# ProiectTSC_schematic.net
KiCad netlist of a schematic drawn in EAGLE
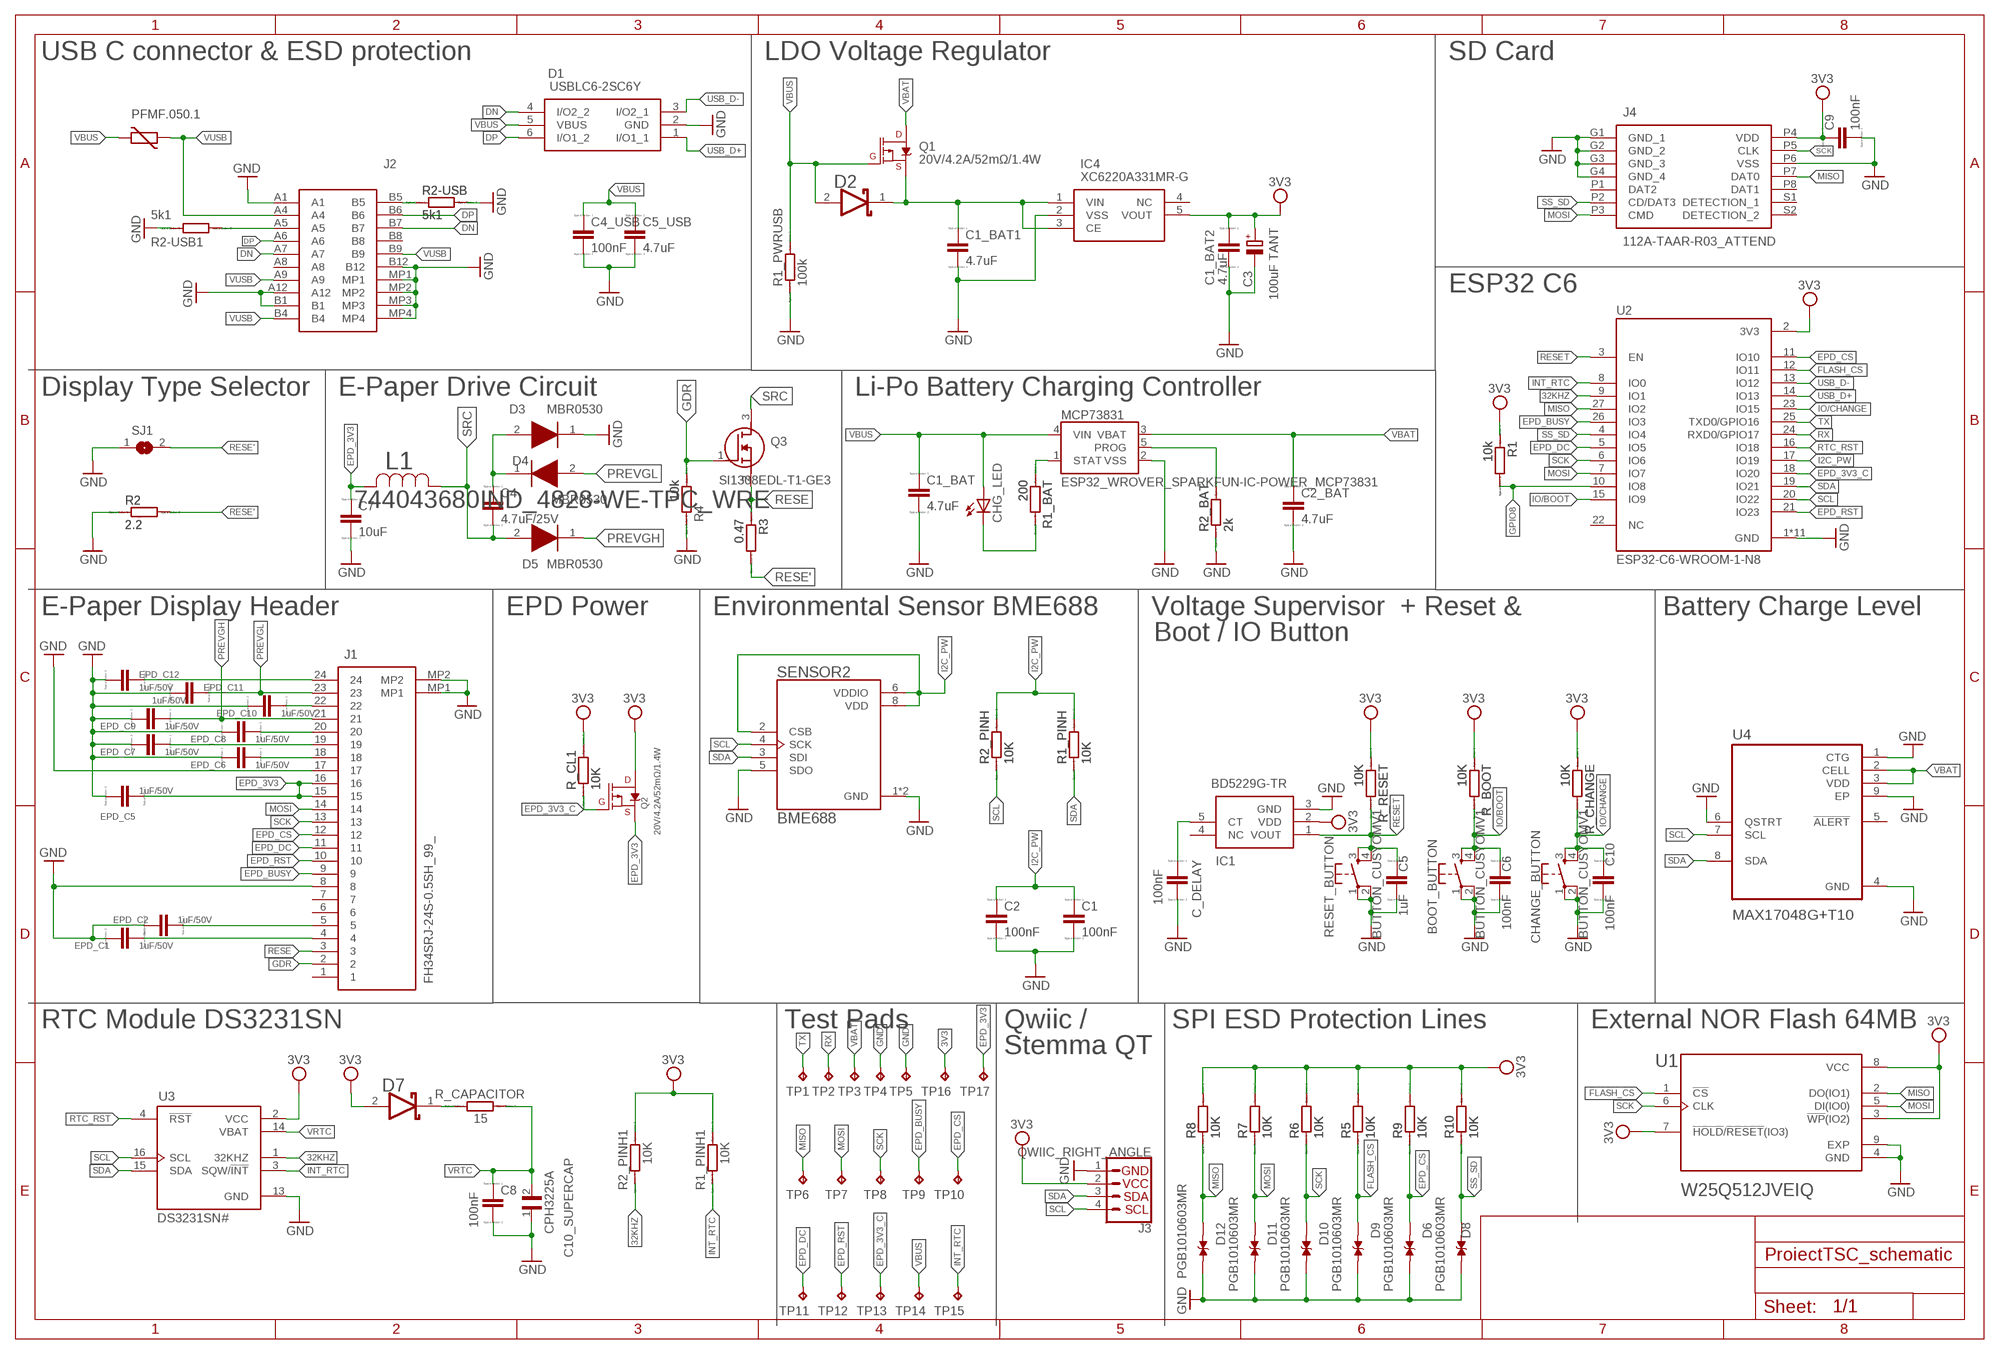
[diagram p0: schematic, sheet 1]

(export (version "E")
  (design (tool "Eeschema 10.0.6"))
  (components
    (comp (ref "BOOT_BUTTON")
      (value "BUTTON_CUSYOMV1")
      (footprint "eagle-import:MYBUTTON")
      (libsource (lib "eagle-import") (part "BUTTON_CUSYOMV1"))
    )
    (comp (ref "C1")
      (value "100nF")
      (footprint "eagle-import:ESP32_WROVER_EAGLE-LTSPICE_C0402")
      (libsource (lib "eagle-import") (part "ESP32_WROVER_EAGLE-LTSPICE_CC0402"))
    )
    (comp (ref "C1_BAT")
      (value "4.7uF")
      (footprint "eagle-import:ESP32_WROVER_EAGLE-LTSPICE_C0402")
      (libsource (lib "eagle-import") (part "ESP32_WROVER_EAGLE-LTSPICE_CC0402"))
    )
    (comp (ref "C1_BAT1")
      (value "4.7uF")
      (footprint "eagle-import:ESP32_WROVER_EAGLE-LTSPICE_C0402")
      (libsource (lib "eagle-import") (part "ESP32_WROVER_EAGLE-LTSPICE_CC0402"))
    )
    (comp (ref "C1_BAT2")
      (value "4.7uF")
      (footprint "eagle-import:ESP32_WROVER_EAGLE-LTSPICE_C0402")
      (libsource (lib "eagle-import") (part "ESP32_WROVER_EAGLE-LTSPICE_CC0402"))
    )
    (comp (ref "C2")
      (value "100nF")
      (footprint "eagle-import:ESP32_WROVER_EAGLE-LTSPICE_C0402")
      (libsource (lib "eagle-import") (part "ESP32_WROVER_EAGLE-LTSPICE_CC0402"))
    )
    (comp (ref "C2_BAT")
      (value "4.7uF")
      (footprint "eagle-import:ESP32_WROVER_EAGLE-LTSPICE_C0402")
      (libsource (lib "eagle-import") (part "ESP32_WROVER_EAGLE-LTSPICE_CC0402"))
    )
    (comp (ref "C3")
      (value "100uF TANT")
      (footprint "eagle-import:RCL_CT3528")
      (libsource (lib "eagle-import") (part "RCL_CPOL-EUCT3528"))
    )
    (comp (ref "C4")
      (value "4.7uF/25V")
      (footprint "eagle-import:ESP32_WROVER_EAGLE-LTSPICE_C0402")
      (libsource (lib "eagle-import") (part "ESP32_WROVER_EAGLE-LTSPICE_CC0402"))
    )
    (comp (ref "C4_USB")
      (value "100nF")
      (footprint "eagle-import:ESP32_WROVER_EAGLE-LTSPICE_C0402")
      (libsource (lib "eagle-import") (part "ESP32_WROVER_EAGLE-LTSPICE_CC0402"))
    )
    (comp (ref "C5")
      (value "1uF")
      (footprint "eagle-import:ESP32_WROVER_EAGLE-LTSPICE_C0402")
      (libsource (lib "eagle-import") (part "ESP32_WROVER_EAGLE-LTSPICE_CC0402"))
    )
    (comp (ref "C5_USB")
      (value "4.7uF")
      (footprint "eagle-import:ESP32_WROVER_EAGLE-LTSPICE_C0402")
      (libsource (lib "eagle-import") (part "ESP32_WROVER_EAGLE-LTSPICE_CC0402"))
    )
    (comp (ref "C6")
      (value "100nF")
      (footprint "eagle-import:ESP32_WROVER_EAGLE-LTSPICE_C0402")
      (libsource (lib "eagle-import") (part "ESP32_WROVER_EAGLE-LTSPICE_CC0402"))
    )
    (comp (ref "C7")
      (value "10uF")
      (footprint "eagle-import:ESP32_WROVER_EAGLE-LTSPICE_C0402")
      (libsource (lib "eagle-import") (part "ESP32_WROVER_EAGLE-LTSPICE_CC0402"))
    )
    (comp (ref "C8")
      (value "100nF")
      (footprint "eagle-import:ESP32_WROVER_EAGLE-LTSPICE_C0402")
      (libsource (lib "eagle-import") (part "ESP32_WROVER_EAGLE-LTSPICE_CC0402"))
    )
    (comp (ref "C9")
      (value "100nF")
      (footprint "eagle-import:ESP32_WROVER_EAGLE-LTSPICE_C0402")
      (libsource (lib "eagle-import") (part "ESP32_WROVER_EAGLE-LTSPICE_CC0402"))
    )
    (comp (ref "C10")
      (value "100nF")
      (footprint "eagle-import:ESP32_WROVER_EAGLE-LTSPICE_C0402")
      (libsource (lib "eagle-import") (part "ESP32_WROVER_EAGLE-LTSPICE_CC0402"))
    )
    (comp (ref "C10_SUPERCAP")
      (value "CPH3225A")
      (footprint "eagle-import:CAPCP3225X100N")
      (fields (field (name "MF") "Seiko Instruments"))
      (libsource (lib "eagle-import") (part "CPH3225A"))
    )
    (comp (ref "CHANGE_BUTTON")
      (value "BUTTON_CUSYOMV1")
      (footprint "eagle-import:MYBUTTON")
      (libsource (lib "eagle-import") (part "BUTTON_CUSYOMV1"))
    )
    (comp (ref "CHG_LED")
      (value "ADAFRUIT_LEDCHIP-LED0603")
      (footprint "eagle-import:ADAFRUIT_CHIP-LED0603")
      (libsource (lib "eagle-import") (part "ADAFRUIT_LEDCHIP-LED0603"))
    )
    (comp (ref "C_DELAY")
      (value "100nF")
      (footprint "eagle-import:ESP32_WROVER_EAGLE-LTSPICE_C0402")
      (libsource (lib "eagle-import") (part "ESP32_WROVER_EAGLE-LTSPICE_CC0402"))
    )
    (comp (ref "D1")
      (value "USBLC6-2SC6Y")
      (footprint "eagle-import:SOT95P280X145-6N")
      (fields (field (name "MF") "STMicroelectronics"))
      (libsource (lib "eagle-import") (part "USBLC6-2SC6Y"))
    )
    (comp (ref "D2")
      (value "SD0805S020S1R0")
      (footprint "eagle-import:ESP32_WROVER_AVX---SD0805S020S1R0_AVX_SD0805S020S1R0_0")
      (fields
        (field (name "DIGIKEY_PART_NUMBER") "478-7800-1-ND")
        (field (name "MF") "AVX")
        (field (name "MOUSER_PART_NUMBER") "581-SD0805S020S1R0")
      )
      (libsource (lib "eagle-import") (part "ESP32_WROVER_AVX---SD0805S020S1R0_AVX_SD0805S020S1R0_0_0AVX_SD0805S020S1R0_0_0"))
    )
    (comp (ref "D3")
      (value "MBR0530")
      (footprint "eagle-import:SOD3716X135N")
      (fields (field (name "MF") "ON Semiconductor"))
      (libsource (lib "eagle-import") (part "MBR0530"))
    )
    (comp (ref "D4")
      (value "MBR0530")
      (footprint "eagle-import:SOD3716X135N")
      (fields (field (name "MF") "ON Semiconductor"))
      (libsource (lib "eagle-import") (part "MBR0530"))
    )
    (comp (ref "D5")
      (value "MBR0530")
      (footprint "eagle-import:SOD3716X135N")
      (fields (field (name "MF") "ON Semiconductor"))
      (libsource (lib "eagle-import") (part "MBR0530"))
    )
    (comp (ref "D6")
      (value "PGB1010603MR")
      (footprint "eagle-import:DIOC1608X36N")
      (fields (field (name "MF") "Littelfuse Inc."))
      (libsource (lib "eagle-import") (part "PGB1010603MR"))
    )
    (comp (ref "D7")
      (value "SD0805S020S1R0")
      (footprint "eagle-import:ESP32_WROVER_AVX---SD0805S020S1R0_AVX_SD0805S020S1R0_0")
      (fields
        (field (name "DIGIKEY_PART_NUMBER") "478-7800-1-ND")
        (field (name "MF") "AVX")
        (field (name "MOUSER_PART_NUMBER") "581-SD0805S020S1R0")
      )
      (libsource (lib "eagle-import") (part "ESP32_WROVER_AVX---SD0805S020S1R0_AVX_SD0805S020S1R0_0_0AVX_SD0805S020S1R0_0_0"))
    )
    (comp (ref "D8")
      (value "PGB1010603MR")
      (footprint "eagle-import:DIOC1608X36N")
      (fields (field (name "MF") "Littelfuse Inc."))
      (libsource (lib "eagle-import") (part "PGB1010603MR"))
    )
    (comp (ref "D9")
      (value "PGB1010603MR")
      (footprint "eagle-import:DIOC1608X36N")
      (fields (field (name "MF") "Littelfuse Inc."))
      (libsource (lib "eagle-import") (part "PGB1010603MR"))
    )
    (comp (ref "D10")
      (value "PGB1010603MR")
      (footprint "eagle-import:DIOC1608X36N")
      (fields (field (name "MF") "Littelfuse Inc."))
      (libsource (lib "eagle-import") (part "PGB1010603MR"))
    )
    (comp (ref "D11")
      (value "PGB1010603MR")
      (footprint "eagle-import:DIOC1608X36N")
      (fields (field (name "MF") "Littelfuse Inc."))
      (libsource (lib "eagle-import") (part "PGB1010603MR"))
    )
    (comp (ref "D12")
      (value "PGB1010603MR")
      (footprint "eagle-import:DIOC1608X36N")
      (fields (field (name "MF") "Littelfuse Inc."))
      (libsource (lib "eagle-import") (part "PGB1010603MR"))
    )
    (comp (ref "EPD_C1")
      (value "1uF/50V")
      (footprint "eagle-import:ESP32_WROVER_EAGLE-LTSPICE_C0402")
      (libsource (lib "eagle-import") (part "ESP32_WROVER_EAGLE-LTSPICE_CC0402"))
    )
    (comp (ref "EPD_C2")
      (value "1uF/50V")
      (footprint "eagle-import:ESP32_WROVER_EAGLE-LTSPICE_C0402")
      (libsource (lib "eagle-import") (part "ESP32_WROVER_EAGLE-LTSPICE_CC0402"))
    )
    (comp (ref "EPD_C5")
      (value "1uF/50V")
      (footprint "eagle-import:ESP32_WROVER_EAGLE-LTSPICE_C0402")
      (libsource (lib "eagle-import") (part "ESP32_WROVER_EAGLE-LTSPICE_CC0402"))
    )
    (comp (ref "EPD_C6")
      (value "1uF/50V")
      (footprint "eagle-import:ESP32_WROVER_EAGLE-LTSPICE_C0402")
      (libsource (lib "eagle-import") (part "ESP32_WROVER_EAGLE-LTSPICE_CC0402"))
    )
    (comp (ref "EPD_C7")
      (value "1uF/50V")
      (footprint "eagle-import:ESP32_WROVER_EAGLE-LTSPICE_C0402")
      (libsource (lib "eagle-import") (part "ESP32_WROVER_EAGLE-LTSPICE_CC0402"))
    )
    (comp (ref "EPD_C8")
      (value "1uF/50V")
      (footprint "eagle-import:ESP32_WROVER_EAGLE-LTSPICE_C0402")
      (libsource (lib "eagle-import") (part "ESP32_WROVER_EAGLE-LTSPICE_CC0402"))
    )
    (comp (ref "EPD_C9")
      (value "1uF/50V")
      (footprint "eagle-import:ESP32_WROVER_EAGLE-LTSPICE_C0402")
      (libsource (lib "eagle-import") (part "ESP32_WROVER_EAGLE-LTSPICE_CC0402"))
    )
    (comp (ref "EPD_C10")
      (value "1uF/50V")
      (footprint "eagle-import:ESP32_WROVER_EAGLE-LTSPICE_C0402")
      (libsource (lib "eagle-import") (part "ESP32_WROVER_EAGLE-LTSPICE_CC0402"))
    )
    (comp (ref "EPD_C11")
      (value "1uF/50V")
      (footprint "eagle-import:ESP32_WROVER_EAGLE-LTSPICE_C0402")
      (libsource (lib "eagle-import") (part "ESP32_WROVER_EAGLE-LTSPICE_CC0402"))
    )
    (comp (ref "EPD_C12")
      (value "1uF/50V")
      (footprint "eagle-import:ESP32_WROVER_EAGLE-LTSPICE_C0402")
      (libsource (lib "eagle-import") (part "ESP32_WROVER_EAGLE-LTSPICE_CC0402"))
    )
    (comp (ref "IC1")
      (value "BD5229G-TR")
      (footprint "eagle-import:SOT95P280X120-5N")
      (fields (field (name "MOUSER_PART_NUMBER") "755-BD5229G-TR"))
      (libsource (lib "eagle-import") (part "BD5229G-TR"))
    )
    (comp (ref "IC4")
      (value "XC6220A331MR-G")
      (footprint "eagle-import:SOT95P280X120-5N")
      (fields (field (name "MOUSER_PART_NUMBER") "865-XC6220A331MR-G"))
      (libsource (lib "eagle-import") (part "XC6220A331MR-G"))
    )
    (comp (ref "J1")
      (value "FH34SRJ-24S-0.5SH_99_")
      (footprint "eagle-import:FH34SRJ24S05SH99")
      (fields
        (field (name "MANUFACTURER_PART_NUMBER") "FH34SRJ-24S-0.5SH(99)")
        (field (name "MOUSER_PART_NUMBER") "798-FH34SRJ24S05SH99")
      )
      (libsource (lib "eagle-import") (part "FH34SRJ-24S-0.5SH_99_"))
    )
    (comp (ref "J2")
      (value "SAMACSYS_PARTS_USB4110-GF-A")
      (footprint "eagle-import:SAMACSYS_PARTS_USB4110GFA")
      (fields
        (field (name "MANUFACTURER_PART_NUMBER") "USB4110-GF-A")
        (field (name "MOUSER_PART_NUMBER") "640-USB4110-GF-A")
      )
      (libsource (lib "eagle-import") (part "SAMACSYS_PARTS_USB4110-GF-A"))
    )
    (comp (ref "J3")
      (value "QWIIC_RIGHT_ANGLE")
      (footprint "eagle-import:JST04_1MM_RA")
      (libsource (lib "eagle-import") (part "QWIIC_CONNECTORJS-1MM"))
    )
    (comp (ref "J4")
      (value "112A-TAAR-R03_ATTEND")
      (footprint "eagle-import:112ATAARR03ATTEND")
      (fields (field (name "MANUFACTURER_PART_NUMBER") "112A-TAAR-R03 ATTEND"))
      (libsource (lib "eagle-import") (part "112A-TAAR-R03_ATTEND"))
    )
    (comp (ref "L1")
      (value "744043680IND_4828-WE-TPC_WRE")
      (footprint "eagle-import:IND_4828-WE-TPC_WRE")
      (fields
        (field (name "MANUFACTURER_PART_NUMBER") "744043680")
        (field (name "COPYRIGHT") "Copyright (C) 2024 Ultra Librarian. All rights reserved.")
      )
      (libsource (lib "eagle-import") (part "744043680IND_4828-WE-TPC_WRE"))
    )
    (comp (ref "MCP73831")
      (value "ESP32_WROVER_SPARKFUN-IC-POWER_MCP73831")
      (footprint "eagle-import:ESP32_WROVER_SPARKFUN-IC-POWER_SOT23-5")
      (libsource (lib "eagle-import") (part "ESP32_WROVER_SPARKFUN-IC-POWER_MCP73831"))
    )
    (comp (ref "PFMF.050.1")
      (value "ESP32C6_VARISTORCN1812")
      (footprint "eagle-import:ESP32C6_VARISTOR_CT_CN1812")
      (libsource (lib "eagle-import") (part "ESP32C6_VARISTORCN1812"))
    )
    (comp (ref "Q1")
      (value "20V/4.2A/52mΩ/1.4W")
      (footprint "eagle-import:ESP32_WROVER_SPARKFUN-DISCRETESEMI_SOT23-3")
      (libsource (lib "eagle-import") (part "ESP32_WROVER_SPARKFUN-DISCRETESEMI_MOSFET_PCH-DMG2305UX-7"))
    )
    (comp (ref "Q2")
      (value "20V/4.2A/52mΩ/1.4W")
      (footprint "eagle-import:ESP32_WROVER_SPARKFUN-DISCRETESEMI_SOT23-3")
      (libsource (lib "eagle-import") (part "ESP32_WROVER_SPARKFUN-DISCRETESEMI_MOSFET_PCH-DMG2305UX-7"))
    )
    (comp (ref "Q3")
      (value "SI1308EDL-T1-GE3")
      (footprint "eagle-import:SOT65P210X110-3N")
      (fields (field (name "MF") "Vishay Siliconix"))
      (libsource (lib "eagle-import") (part "SI1308EDL-T1-GE3"))
    )
    (comp (ref "R1")
      (value "10k")
      (footprint "eagle-import:ESP32_WROVER_EAGLE-LTSPICE_R0402")
      (libsource (lib "eagle-import") (part "ESP32_WROVER_EAGLE-LTSPICE_RR0402"))
    )
    (comp (ref "R1_BAT")
      (value "200")
      (footprint "eagle-import:ESP32_WROVER_EAGLE-LTSPICE_R0402")
      (libsource (lib "eagle-import") (part "ESP32_WROVER_EAGLE-LTSPICE_RR0402"))
    )
    (comp (ref "R1_PINH")
      (value "10K")
      (footprint "eagle-import:ESP32_WROVER_EAGLE-LTSPICE_R0402")
      (libsource (lib "eagle-import") (part "ESP32_WROVER_EAGLE-LTSPICE_RR0402"))
    )
    (comp (ref "R1_PINH1")
      (value "10K")
      (footprint "eagle-import:ESP32_WROVER_EAGLE-LTSPICE_R0402")
      (libsource (lib "eagle-import") (part "ESP32_WROVER_EAGLE-LTSPICE_RR0402"))
    )
    (comp (ref "R1_PWRUSB")
      (value "100k")
      (footprint "eagle-import:ESP32_WROVER_EAGLE-LTSPICE_R0402")
      (libsource (lib "eagle-import") (part "ESP32_WROVER_EAGLE-LTSPICE_RR0402"))
    )
    (comp (ref "R2")
      (value "2.2")
      (footprint "eagle-import:ESP32_WROVER_EAGLE-LTSPICE_R0402")
      (libsource (lib "eagle-import") (part "ESP32_WROVER_EAGLE-LTSPICE_RR0402"))
    )
    (comp (ref "R2-USB")
      (value "5k1")
      (footprint "eagle-import:ESP32_WROVER_EAGLE-LTSPICE_R0402")
      (libsource (lib "eagle-import") (part "ESP32_WROVER_EAGLE-LTSPICE_RR0402"))
    )
    (comp (ref "R2-USB1")
      (value "5k1")
      (footprint "eagle-import:ESP32_WROVER_EAGLE-LTSPICE_R0402")
      (libsource (lib "eagle-import") (part "ESP32_WROVER_EAGLE-LTSPICE_RR0402"))
    )
    (comp (ref "R2_BAT")
      (value "2k")
      (footprint "eagle-import:ESP32_WROVER_EAGLE-LTSPICE_R0402")
      (libsource (lib "eagle-import") (part "ESP32_WROVER_EAGLE-LTSPICE_RR0402"))
    )
    (comp (ref "R2_PINH")
      (value "10K")
      (footprint "eagle-import:ESP32_WROVER_EAGLE-LTSPICE_R0402")
      (libsource (lib "eagle-import") (part "ESP32_WROVER_EAGLE-LTSPICE_RR0402"))
    )
    (comp (ref "R2_PINH1")
      (value "10K")
      (footprint "eagle-import:ESP32_WROVER_EAGLE-LTSPICE_R0402")
      (libsource (lib "eagle-import") (part "ESP32_WROVER_EAGLE-LTSPICE_RR0402"))
    )
    (comp (ref "R3")
      (value "0.47")
      (footprint "eagle-import:ESP32_WROVER_EAGLE-LTSPICE_R0402")
      (libsource (lib "eagle-import") (part "ESP32_WROVER_EAGLE-LTSPICE_RR0402"))
    )
    (comp (ref "R4")
      (value "10k")
      (footprint "eagle-import:ESP32_WROVER_EAGLE-LTSPICE_R0402")
      (libsource (lib "eagle-import") (part "ESP32_WROVER_EAGLE-LTSPICE_RR0402"))
    )
    (comp (ref "R5")
      (value "10K")
      (footprint "eagle-import:ESP32_WROVER_EAGLE-LTSPICE_R0402")
      (libsource (lib "eagle-import") (part "ESP32_WROVER_EAGLE-LTSPICE_RR0402"))
    )
    (comp (ref "R6")
      (value "10K")
      (footprint "eagle-import:ESP32_WROVER_EAGLE-LTSPICE_R0402")
      (libsource (lib "eagle-import") (part "ESP32_WROVER_EAGLE-LTSPICE_RR0402"))
    )
    (comp (ref "R7")
      (value "10K")
      (footprint "eagle-import:ESP32_WROVER_EAGLE-LTSPICE_R0402")
      (libsource (lib "eagle-import") (part "ESP32_WROVER_EAGLE-LTSPICE_RR0402"))
    )
    (comp (ref "R8")
      (value "10K")
      (footprint "eagle-import:ESP32_WROVER_EAGLE-LTSPICE_R0402")
      (libsource (lib "eagle-import") (part "ESP32_WROVER_EAGLE-LTSPICE_RR0402"))
    )
    (comp (ref "R9")
      (value "10K")
      (footprint "eagle-import:ESP32_WROVER_EAGLE-LTSPICE_R0402")
      (libsource (lib "eagle-import") (part "ESP32_WROVER_EAGLE-LTSPICE_RR0402"))
    )
    (comp (ref "R10")
      (value "10K")
      (footprint "eagle-import:ESP32_WROVER_EAGLE-LTSPICE_R0402")
      (libsource (lib "eagle-import") (part "ESP32_WROVER_EAGLE-LTSPICE_RR0402"))
    )
    (comp (ref "RESET_BUTTON")
      (value "BUTTON_CUSYOMV1")
      (footprint "eagle-import:MYBUTTON")
      (libsource (lib "eagle-import") (part "BUTTON_CUSYOMV1"))
    )
    (comp (ref "R_BOOT")
      (value "10K")
      (footprint "eagle-import:ESP32_WROVER_EAGLE-LTSPICE_R0402")
      (libsource (lib "eagle-import") (part "ESP32_WROVER_EAGLE-LTSPICE_RR0402"))
    )
    (comp (ref "R_CAPACITOR")
      (value "15")
      (footprint "eagle-import:ESP32_WROVER_EAGLE-LTSPICE_R0402")
      (libsource (lib "eagle-import") (part "ESP32_WROVER_EAGLE-LTSPICE_RR0402"))
    )
    (comp (ref "R_CHANGE")
      (value "10K")
      (footprint "eagle-import:ESP32_WROVER_EAGLE-LTSPICE_R0402")
      (libsource (lib "eagle-import") (part "ESP32_WROVER_EAGLE-LTSPICE_RR0402"))
    )
    (comp (ref "R_CL1")
      (value "10K")
      (footprint "eagle-import:ESP32_WROVER_EAGLE-LTSPICE_R0402")
      (libsource (lib "eagle-import") (part "ESP32_WROVER_EAGLE-LTSPICE_RR0402"))
    )
    (comp (ref "R_RESET")
      (value "10K")
      (footprint "eagle-import:ESP32_WROVER_EAGLE-LTSPICE_R0402")
      (libsource (lib "eagle-import") (part "ESP32_WROVER_EAGLE-LTSPICE_RR0402"))
    )
    (comp (ref "SENSOR2")
      (value "BME688")
      (footprint "eagle-import:ESP32_WROVER_BME680_PSON80P300X300X100-8N")
      (fields (field (name "MF") "Bosch Sensortec") (field (name "MP") "BME680"))
      (libsource (lib "eagle-import") (part "ESP32_WROVER_BME680_BME680"))
    )
    (comp (ref "SJ1") (value "SJ") (footprint "eagle-import:SJ") (libsource (lib "eagle-import") (part "SJ")))
    (comp (ref "TP1")
      (value "TPTP20R")
      (footprint "eagle-import:TP20R")
      (libsource (lib "eagle-import") (part "TPTP20R"))
    )
    (comp (ref "TP2")
      (value "TPTP20R")
      (footprint "eagle-import:TP20R")
      (libsource (lib "eagle-import") (part "TPTP20R"))
    )
    (comp (ref "TP3")
      (value "TPTP20R")
      (footprint "eagle-import:TP20R")
      (libsource (lib "eagle-import") (part "TPTP20R"))
    )
    (comp (ref "TP4")
      (value "TPTP20R")
      (footprint "eagle-import:TP20R")
      (libsource (lib "eagle-import") (part "TPTP20R"))
    )
    (comp (ref "TP5")
      (value "TPTP20R")
      (footprint "eagle-import:TP20R")
      (libsource (lib "eagle-import") (part "TPTP20R"))
    )
    (comp (ref "TP6")
      (value "TPTP20R")
      (footprint "eagle-import:TP20R")
      (libsource (lib "eagle-import") (part "TPTP20R"))
    )
    (comp (ref "TP7")
      (value "TPTP20R")
      (footprint "eagle-import:TP20R")
      (libsource (lib "eagle-import") (part "TPTP20R"))
    )
    (comp (ref "TP8")
      (value "TPTP20R")
      (footprint "eagle-import:TP20R")
      (libsource (lib "eagle-import") (part "TPTP20R"))
    )
    (comp (ref "TP9")
      (value "TPTP20R")
      (footprint "eagle-import:TP20R")
      (libsource (lib "eagle-import") (part "TPTP20R"))
    )
    (comp (ref "TP10")
      (value "TPTP20R")
      (footprint "eagle-import:TP20R")
      (libsource (lib "eagle-import") (part "TPTP20R"))
    )
    (comp (ref "TP11")
      (value "TPTP20R")
      (footprint "eagle-import:TP20R")
      (libsource (lib "eagle-import") (part "TPTP20R"))
    )
    (comp (ref "TP12")
      (value "TPTP20R")
      (footprint "eagle-import:TP20R")
      (libsource (lib "eagle-import") (part "TPTP20R"))
    )
    (comp (ref "TP13")
      (value "TPTP20R")
      (footprint "eagle-import:TP20R")
      (libsource (lib "eagle-import") (part "TPTP20R"))
    )
    (comp (ref "TP14")
      (value "TPTP20R")
      (footprint "eagle-import:TP20R")
      (libsource (lib "eagle-import") (part "TPTP20R"))
    )
    (comp (ref "TP15")
      (value "TPTP20R")
      (footprint "eagle-import:TP20R")
      (libsource (lib "eagle-import") (part "TPTP20R"))
    )
    (comp (ref "TP16")
      (value "TPTP20R")
      (footprint "eagle-import:TP20R")
      (libsource (lib "eagle-import") (part "TPTP20R"))
    )
    (comp (ref "TP17")
      (value "TPTP20R")
      (footprint "eagle-import:TP20R")
      (libsource (lib "eagle-import") (part "TPTP20R"))
    )
    (comp (ref "U1")
      (value "W25Q512JVEIQ")
      (footprint "eagle-import:SON127P600X800X80-9N")
      (fields (field (name "MF") "Winbond Electronics"))
      (libsource (lib "eagle-import") (part "W25Q512JVEIQ"))
    )
    (comp (ref "U2")
      (value "ESP32-C6-WROOM-1-N8")
      (footprint "eagle-import:XCVR_ESP32-C6-WROOM-1-N8")
      (fields (field (name "MF") "Espressif Systems"))
      (libsource (lib "eagle-import") (part "ESP32-C6-WROOM-1-N8"))
    )
    (comp (ref "U3")
      (value "DS3231SN#")
      (footprint "eagle-import:SOIC127P1032X265-16N")
      (fields (field (name "MF") "Analog Devices"))
      (libsource (lib "eagle-import") (part "DS3231SN#"))
    )
    (comp (ref "U4")
      (value "MAX17048G+T10")
      (footprint "eagle-import:SON50P200X200X80-9N")
      (fields (field (name "MF") "Analog Devices"))
      (libsource (lib "eagle-import") (part "MAX17048G+T10"))
    )
  )
  (nets
    (net (code "1") (name "3V3") (class "Default")
      (node (ref "C1_BAT2") (pin "1") (pinfunction "1_1") (pintype "passive"))
      (node (ref "C3") (pin "+") (pinfunction "+_+") (pintype "passive"))
      (node (ref "C9") (pin "1") (pinfunction "1_1") (pintype "passive"))
      (node (ref "D7") (pin "2") (pinfunction "ANODE_2") (pintype "bidirectional"))
      (node (ref "IC1") (pin "2") (pinfunction "VDD_2") (pintype "bidirectional"))
      (node (ref "IC4") (pin "5") (pinfunction "VOUT_5") (pintype "bidirectional"))
      (node (ref "J3") (pin "2") (pinfunction "2_2") (pintype "power_in"))
      (node (ref "J4") (pin "P4") (pinfunction "VDD_P4") (pintype "bidirectional"))
      (node (ref "Q2") (pin "3") (pinfunction "D_3") (pintype "bidirectional"))
      (node (ref "R1") (pin "1") (pinfunction "1_1") (pintype "passive"))
      (node (ref "R10") (pin "2") (pinfunction "2_2") (pintype "passive"))
      (node (ref "R1_PINH1") (pin "2") (pinfunction "2_2") (pintype "passive"))
      (node (ref "R2_PINH1") (pin "2") (pinfunction "2_2") (pintype "passive"))
      (node (ref "R5") (pin "2") (pinfunction "2_2") (pintype "passive"))
      (node (ref "R6") (pin "2") (pinfunction "2_2") (pintype "passive"))
      (node (ref "R7") (pin "2") (pinfunction "2_2") (pintype "passive"))
      (node (ref "R8") (pin "2") (pinfunction "2_2") (pintype "passive"))
      (node (ref "R9") (pin "2") (pinfunction "2_2") (pintype "passive"))
      (node (ref "R_BOOT") (pin "1") (pinfunction "1_1") (pintype "passive"))
      (node (ref "R_CHANGE") (pin "1") (pinfunction "1_1") (pintype "passive"))
      (node (ref "R_CL1") (pin "2") (pinfunction "2_2") (pintype "passive"))
      (node (ref "R_RESET") (pin "1") (pinfunction "1_1") (pintype "passive"))
      (node (ref "TP16") (pin "TP") (pinfunction "TP_TP") (pintype "input"))
      (node (ref "U1") (pin "3") (pinfunction "~{WP}(IO2)_3") (pintype "bidirectional"))
      (node (ref "U1") (pin "7") (pinfunction "~{HOLD}/~{RESET}(IO3)_7") (pintype "bidirectional"))
      (node (ref "U1") (pin "8") (pinfunction "VCC_8") (pintype "power_in"))
      (node (ref "U2") (pin "2") (pinfunction "3V3_2") (pintype "power_in"))
      (node (ref "U3") (pin "2") (pinfunction "VCC_2") (pintype "power_in"))
    )
    (net (code "2") (name "32KHZ") (class "Default")
      (node (ref "R2_PINH1") (pin "1") (pinfunction "1_1") (pintype "passive"))
      (node (ref "U2") (pin "9") (pinfunction "IO1_9") (pintype "bidirectional"))
      (node (ref "U3") (pin "1") (pinfunction "32KHZ_1") (pintype "output"))
    )
    (net (code "3") (name "DN") (class "Default")
      (node (ref "D1") (pin "4") (pinfunction "I/O2_2_4") (pintype "bidirectional"))
      (node (ref "J2") (pin "A7") (pinfunction "A7_A7") (pintype "bidirectional"))
      (node (ref "J2") (pin "B7") (pinfunction "B7_B7") (pintype "bidirectional"))
    )
    (net (code "4") (name "DP") (class "Default")
      (node (ref "D1") (pin "6") (pinfunction "I/O1_2_6") (pintype "bidirectional"))
      (node (ref "J2") (pin "A6") (pinfunction "A6_A6") (pintype "bidirectional"))
      (node (ref "J2") (pin "B6") (pinfunction "B6_B6") (pintype "bidirectional"))
    )
    (net (code "5") (name "EPD_3V3") (class "Default")
      (node (ref "C7") (pin "1") (pinfunction "1_1") (pintype "passive"))
      (node (ref "EPD_C5") (pin "1") (pinfunction "1_1") (pintype "passive"))
      (node (ref "J1") (pin "15") (pinfunction "15_15") (pintype "bidirectional"))
      (node (ref "J1") (pin "16") (pinfunction "16_16") (pintype "bidirectional"))
      (node (ref "L1") (pin "2") (pinfunction "2_2") (pintype "passive"))
      (node (ref "Q2") (pin "2") (pinfunction "S_2") (pintype "bidirectional"))
      (node (ref "TP17") (pin "TP") (pinfunction "TP_TP") (pintype "input"))
    )
    (net (code "6") (name "EPD_3V3_C") (class "Default")
      (node (ref "Q2") (pin "1") (pinfunction "G_1") (pintype "bidirectional"))
      (node (ref "R_CL1") (pin "1") (pinfunction "1_1") (pintype "passive"))
      (node (ref "TP13") (pin "TP") (pinfunction "TP_TP") (pintype "input"))
      (node (ref "U2") (pin "18") (pinfunction "IO20_18") (pintype "bidirectional"))
    )
    (net (code "7") (name "EPD_BUSY") (class "Default")
      (node (ref "J1") (pin "9") (pinfunction "9_9") (pintype "bidirectional"))
      (node (ref "TP9") (pin "TP") (pinfunction "TP_TP") (pintype "input"))
      (node (ref "U2") (pin "26") (pinfunction "IO3_26") (pintype "bidirectional"))
    )
    (net (code "8") (name "EPD_CS") (class "Default")
      (node (ref "D6") (pin "1") (pinfunction "1_1") (pintype "passive"))
      (node (ref "J1") (pin "12") (pinfunction "12_12") (pintype "bidirectional"))
      (node (ref "R9") (pin "1") (pinfunction "1_1") (pintype "passive"))
      (node (ref "TP10") (pin "TP") (pinfunction "TP_TP") (pintype "input"))
      (node (ref "U2") (pin "11") (pinfunction "IO10_11") (pintype "bidirectional"))
    )
    (net (code "9") (name "EPD_DC") (class "Default")
      (node (ref "J1") (pin "11") (pinfunction "11_11") (pintype "bidirectional"))
      (node (ref "TP11") (pin "TP") (pinfunction "TP_TP") (pintype "input"))
      (node (ref "U2") (pin "5") (pinfunction "IO5_5") (pintype "bidirectional"))
    )
    (net (code "10") (name "EPD_RST") (class "Default")
      (node (ref "J1") (pin "10") (pinfunction "10_10") (pintype "bidirectional"))
      (node (ref "TP12") (pin "TP") (pinfunction "TP_TP") (pintype "input"))
      (node (ref "U2") (pin "21") (pinfunction "IO23_21") (pintype "bidirectional"))
    )
    (net (code "11") (name "FLASH_CS") (class "Default")
      (node (ref "D9") (pin "1") (pinfunction "1_1") (pintype "passive"))
      (node (ref "R5") (pin "1") (pinfunction "1_1") (pintype "passive"))
      (node (ref "U1") (pin "1") (pinfunction "~{CS}_1") (pintype "input"))
      (node (ref "U2") (pin "12") (pinfunction "IO11_12") (pintype "bidirectional"))
    )
    (net (code "12") (name "GDR") (class "Default")
      (node (ref "J1") (pin "2") (pinfunction "2_2") (pintype "bidirectional"))
      (node (ref "Q3") (pin "1") (pinfunction "G_1") (pintype "bidirectional"))
      (node (ref "R4") (pin "1") (pinfunction "1_1") (pintype "passive"))
    )
    (net (code "13") (name "GND") (class "Default")
      (node (ref "BOOT_BUTTON") (pin "1") (pinfunction "1_1") (pintype "passive"))
      (node (ref "BOOT_BUTTON") (pin "2") (pinfunction "2_2") (pintype "passive"))
      (node (ref "C1") (pin "2") (pinfunction "2_2") (pintype "passive"))
      (node (ref "C10") (pin "2") (pinfunction "2_2") (pintype "passive"))
      (node (ref "C10_SUPERCAP") (pin "1") (pinfunction "1_1") (pintype "passive"))
      (node (ref "C1_BAT") (pin "2") (pinfunction "2_2") (pintype "passive"))
      (node (ref "C1_BAT1") (pin "2") (pinfunction "2_2") (pintype "passive"))
      (node (ref "C1_BAT2") (pin "2") (pinfunction "2_2") (pintype "passive"))
      (node (ref "C2") (pin "2") (pinfunction "2_2") (pintype "passive"))
      (node (ref "C2_BAT") (pin "2") (pinfunction "2_2") (pintype "passive"))
      (node (ref "C3") (pin "-") (pinfunction "-_-") (pintype "passive"))
      (node (ref "C4_USB") (pin "2") (pinfunction "2_2") (pintype "passive"))
      (node (ref "C5") (pin "2") (pinfunction "2_2") (pintype "passive"))
      (node (ref "C5_USB") (pin "2") (pinfunction "2_2") (pintype "passive"))
      (node (ref "C6") (pin "2") (pinfunction "2_2") (pintype "passive"))
      (node (ref "C7") (pin "2") (pinfunction "2_2") (pintype "passive"))
      (node (ref "C8") (pin "2") (pinfunction "2_2") (pintype "passive"))
      (node (ref "C9") (pin "2") (pinfunction "2_2") (pintype "passive"))
      (node (ref "CHANGE_BUTTON") (pin "1") (pinfunction "1_1") (pintype "passive"))
      (node (ref "CHANGE_BUTTON") (pin "2") (pinfunction "2_2") (pintype "passive"))
      (node (ref "C_DELAY") (pin "2") (pinfunction "2_2") (pintype "passive"))
      (node (ref "D1") (pin "2") (pinfunction "GND_2") (pintype "bidirectional"))
      (node (ref "D10") (pin "2") (pinfunction "2_2") (pintype "passive"))
      (node (ref "D11") (pin "2") (pinfunction "2_2") (pintype "passive"))
      (node (ref "D12") (pin "2") (pinfunction "2_2") (pintype "passive"))
      (node (ref "D3") (pin "1") (pinfunction "K_1") (pintype "bidirectional"))
      (node (ref "D6") (pin "2") (pinfunction "2_2") (pintype "passive"))
      (node (ref "D8") (pin "2") (pinfunction "2_2") (pintype "passive"))
      (node (ref "D9") (pin "2") (pinfunction "2_2") (pintype "passive"))
      (node (ref "EPD_C1") (pin "2") (pinfunction "2_2") (pintype "passive"))
      (node (ref "EPD_C10") (pin "2") (pinfunction "2_2") (pintype "passive"))
      (node (ref "EPD_C11") (pin "2") (pinfunction "2_2") (pintype "passive"))
      (node (ref "EPD_C12") (pin "2") (pinfunction "2_2") (pintype "passive"))
      (node (ref "EPD_C2") (pin "2") (pinfunction "2_2") (pintype "passive"))
      (node (ref "EPD_C5") (pin "2") (pinfunction "2_2") (pintype "passive"))
      (node (ref "EPD_C6") (pin "2") (pinfunction "2_2") (pintype "passive"))
      (node (ref "EPD_C7") (pin "2") (pinfunction "2_2") (pintype "passive"))
      (node (ref "EPD_C8") (pin "2") (pinfunction "2_2") (pintype "passive"))
      (node (ref "EPD_C9") (pin "2") (pinfunction "2_2") (pintype "passive"))
      (node (ref "IC1") (pin "3") (pinfunction "GND_3") (pintype "bidirectional"))
      (node (ref "IC4") (pin "2") (pinfunction "VSS_2") (pintype "bidirectional"))
      (node (ref "J1") (pin "17") (pinfunction "17_17") (pintype "bidirectional"))
      (node (ref "J1") (pin "8") (pinfunction "8_8") (pintype "bidirectional"))
      (node (ref "J1") (pin "MP1") (pinfunction "MP1_MP1") (pintype "bidirectional"))
      (node (ref "J1") (pin "MP2") (pinfunction "MP2_MP2") (pintype "bidirectional"))
      (node (ref "J2") (pin "A1") (pinfunction "A1_A1") (pintype "bidirectional"))
      (node (ref "J2") (pin "A12") (pinfunction "A12_A12") (pintype "bidirectional"))
      (node (ref "J2") (pin "B1") (pinfunction "B1_B1") (pintype "bidirectional"))
      (node (ref "J2") (pin "B12") (pinfunction "B12_B12") (pintype "bidirectional"))
      (node (ref "J2") (pin "MP1") (pinfunction "MP1_MP1") (pintype "bidirectional"))
      (node (ref "J2") (pin "MP2") (pinfunction "MP2_MP2") (pintype "bidirectional"))
      (node (ref "J2") (pin "MP3") (pinfunction "MP3_MP3") (pintype "bidirectional"))
      (node (ref "J2") (pin "MP4") (pinfunction "MP4_MP4") (pintype "bidirectional"))
      (node (ref "J3") (pin "1") (pinfunction "1_1") (pintype "power_in"))
      (node (ref "J4") (pin "G1") (pinfunction "GND_1_G1") (pintype "bidirectional"))
      (node (ref "J4") (pin "G2") (pinfunction "GND_2_G2") (pintype "bidirectional"))
      (node (ref "J4") (pin "G3") (pinfunction "GND_3_G3") (pintype "bidirectional"))
      (node (ref "J4") (pin "G4") (pinfunction "GND_4_G4") (pintype "bidirectional"))
      (node (ref "J4") (pin "P6") (pinfunction "VSS_P6") (pintype "bidirectional"))
      (node (ref "MCP73831") (pin "2") (pinfunction "VSS_2") (pintype "power_in"))
      (node (ref "R1_PWRUSB") (pin "1") (pinfunction "1_1") (pintype "passive"))
      (node (ref "R2") (pin "1") (pinfunction "1_1") (pintype "passive"))
      (node (ref "R2-USB") (pin "2") (pinfunction "2_2") (pintype "passive"))
      (node (ref "R2-USB1") (pin "1") (pinfunction "1_1") (pintype "passive"))
      (node (ref "R2_BAT") (pin "1") (pinfunction "1_1") (pintype "passive"))
      (node (ref "R4") (pin "2") (pinfunction "2_2") (pintype "passive"))
      (node (ref "RESET_BUTTON") (pin "1") (pinfunction "1_1") (pintype "passive"))
      (node (ref "RESET_BUTTON") (pin "2") (pinfunction "2_2") (pintype "passive"))
      (node (ref "SENSOR2") (pin "1") (pinfunction "GND_1") (pintype "power_in"))
      (node (ref "SENSOR2") (pin "5") (pinfunction "SDO_5") (pintype "bidirectional"))
      (node (ref "SENSOR2") (pin "7") (pinfunction "GND_7") (pintype "power_in"))
      (node (ref "SJ1") (pin "1") (pinfunction "1_1") (pintype "passive"))
      (node (ref "TP4") (pin "TP") (pinfunction "TP_TP") (pintype "input"))
      (node (ref "TP5") (pin "TP") (pinfunction "TP_TP") (pintype "input"))
      (node (ref "U1") (pin "4") (pinfunction "GND_4") (pintype "power_in"))
      (node (ref "U1") (pin "9") (pinfunction "EXP_9") (pintype "passive"))
      (node (ref "U2") (pin "1") (pinfunction "GND_1") (pintype "power_in"))
      (node (ref "U2") (pin "28") (pinfunction "GND_28") (pintype "power_in"))
      (node (ref "U2") (pin "29_1") (pinfunction "GND_29_1") (pintype "power_in"))
      (node (ref "U2") (pin "29_2") (pinfunction "GND_29_2") (pintype "power_in"))
      (node (ref "U2") (pin "29_3") (pinfunction "GND_29_3") (pintype "power_in"))
      (node (ref "U2") (pin "29_4") (pinfunction "GND_29_4") (pintype "power_in"))
      (node (ref "U2") (pin "29_5") (pinfunction "GND_29_5") (pintype "power_in"))
      (node (ref "U2") (pin "29_6") (pinfunction "GND_29_6") (pintype "power_in"))
      (node (ref "U2") (pin "29_7") (pinfunction "GND_29_7") (pintype "power_in"))
      (node (ref "U2") (pin "29_8") (pinfunction "GND_29_8") (pintype "power_in"))
      (node (ref "U2") (pin "29_9") (pinfunction "GND_29_9") (pintype "power_in"))
      (node (ref "U3") (pin "13") (pinfunction "GND_13") (pintype "power_in"))
      (node (ref "U4") (pin "1") (pinfunction "CTG_1") (pintype "power_in"))
      (node (ref "U4") (pin "4") (pinfunction "GND_4") (pintype "power_in"))
      (node (ref "U4") (pin "6") (pinfunction "QSTRT_6") (pintype "input"))
      (node (ref "U4") (pin "9") (pinfunction "EP_9") (pintype "power_in"))
    )
    (net (code "14") (name "GPIO8") (class "Default")
      (node (ref "R1") (pin "2") (pinfunction "2_2") (pintype "passive"))
      (node (ref "U2") (pin "10") (pinfunction "IO8_10") (pintype "bidirectional"))
    )
    (net (code "15") (name "I2C_PW") (class "Default")
      (node (ref "C1") (pin "1") (pinfunction "1_1") (pintype "passive"))
      (node (ref "C2") (pin "1") (pinfunction "1_1") (pintype "passive"))
      (node (ref "R1_PINH") (pin "2") (pinfunction "2_2") (pintype "passive"))
      (node (ref "R2_PINH") (pin "2") (pinfunction "2_2") (pintype "passive"))
      (node (ref "SENSOR2") (pin "2") (pinfunction "CSB_2") (pintype "input"))
      (node (ref "SENSOR2") (pin "6") (pinfunction "VDDIO_6") (pintype "power_in"))
      (node (ref "SENSOR2") (pin "8") (pinfunction "VDD_8") (pintype "power_in"))
      (node (ref "U2") (pin "17") (pinfunction "IO19_17") (pintype "bidirectional"))
    )
    (net (code "16") (name "INT_RTC") (class "Default")
      (node (ref "R1_PINH1") (pin "1") (pinfunction "1_1") (pintype "passive"))
      (node (ref "TP15") (pin "TP") (pinfunction "TP_TP") (pintype "input"))
      (node (ref "U2") (pin "8") (pinfunction "IO0_8") (pintype "bidirectional"))
      (node (ref "U3") (pin "3") (pinfunction "SQW/~{INT}_3") (pintype "output"))
    )
    (net (code "17") (name "IO{slash}BOOT") (class "Default")
      (node (ref "BOOT_BUTTON") (pin "3") (pinfunction "3_3") (pintype "passive"))
      (node (ref "BOOT_BUTTON") (pin "4") (pinfunction "4_4") (pintype "passive"))
      (node (ref "C6") (pin "1") (pinfunction "1_1") (pintype "passive"))
      (node (ref "R_BOOT") (pin "2") (pinfunction "2_2") (pintype "passive"))
      (node (ref "U2") (pin "15") (pinfunction "IO9_15") (pintype "bidirectional"))
    )
    (net (code "18") (name "IO{slash}CHANGE") (class "Default")
      (node (ref "C10") (pin "1") (pinfunction "1_1") (pintype "passive"))
      (node (ref "CHANGE_BUTTON") (pin "3") (pinfunction "3_3") (pintype "passive"))
      (node (ref "CHANGE_BUTTON") (pin "4") (pinfunction "4_4") (pintype "passive"))
      (node (ref "R_CHANGE") (pin "2") (pinfunction "2_2") (pintype "passive"))
      (node (ref "U2") (pin "23") (pinfunction "IO15_23") (pintype "bidirectional"))
    )
    (net (code "19") (name "MISO") (class "Default")
      (node (ref "D12") (pin "1") (pinfunction "1_1") (pintype "passive"))
      (node (ref "J4") (pin "P7") (pinfunction "DAT0_P7") (pintype "bidirectional"))
      (node (ref "R8") (pin "1") (pinfunction "1_1") (pintype "passive"))
      (node (ref "TP6") (pin "TP") (pinfunction "TP_TP") (pintype "input"))
      (node (ref "U1") (pin "2") (pinfunction "DO(IO1)_2") (pintype "bidirectional"))
      (node (ref "U2") (pin "27") (pinfunction "IO2_27") (pintype "bidirectional"))
    )
    (net (code "20") (name "MOSI") (class "Default")
      (node (ref "D11") (pin "1") (pinfunction "1_1") (pintype "passive"))
      (node (ref "J1") (pin "14") (pinfunction "14_14") (pintype "bidirectional"))
      (node (ref "J4") (pin "P3") (pinfunction "CMD_P3") (pintype "bidirectional"))
      (node (ref "R7") (pin "1") (pinfunction "1_1") (pintype "passive"))
      (node (ref "TP7") (pin "TP") (pinfunction "TP_TP") (pintype "input"))
      (node (ref "U1") (pin "5") (pinfunction "DI(IO0)_5") (pintype "bidirectional"))
      (node (ref "U2") (pin "7") (pinfunction "IO7_7") (pintype "bidirectional"))
    )
    (net (code "21") (name "Net-(CHG_LED-PadC)") (class "Default")
      (node (ref "CHG_LED") (pin "C") (pinfunction "C_C") (pintype "passive"))
      (node (ref "R1_BAT") (pin "2") (pinfunction "2_2") (pintype "passive"))
    )
    (net (code "22") (name "Net-(D2-CATHODE)") (class "Default")
      (node (ref "C1_BAT1") (pin "1") (pinfunction "1_1") (pintype "passive"))
      (node (ref "D2") (pin "1") (pinfunction "CATHODE_1") (pintype "bidirectional"))
      (node (ref "IC4") (pin "1") (pinfunction "VIN_1") (pintype "bidirectional"))
      (node (ref "IC4") (pin "3") (pinfunction "CE_3") (pintype "bidirectional"))
      (node (ref "Q1") (pin "2") (pinfunction "S_2") (pintype "bidirectional"))
    )
    (net (code "23") (name "Net-(D3-A)") (class "Default")
      (node (ref "C4") (pin "1") (pinfunction "1_1") (pintype "passive"))
      (node (ref "D3") (pin "2") (pinfunction "A_2") (pintype "bidirectional"))
      (node (ref "D4") (pin "1") (pinfunction "K_1") (pintype "bidirectional"))
    )
    (net (code "24") (name "Net-(D7-CATHODE)") (class "Default")
      (node (ref "D7") (pin "1") (pinfunction "CATHODE_1") (pintype "bidirectional"))
      (node (ref "R_CAPACITOR") (pin "1") (pinfunction "1_1") (pintype "passive"))
    )
    (net (code "25") (name "Net-(EPD_C1-Pad1)") (class "Default")
      (node (ref "EPD_C1") (pin "1") (pinfunction "1_1") (pintype "passive"))
      (node (ref "J1") (pin "4") (pinfunction "4_4") (pintype "bidirectional"))
    )
    (net (code "26") (name "Net-(EPD_C2-Pad1)") (class "Default")
      (node (ref "EPD_C2") (pin "1") (pinfunction "1_1") (pintype "passive"))
      (node (ref "J1") (pin "5") (pinfunction "5_5") (pintype "bidirectional"))
    )
    (net (code "27") (name "Net-(EPD_C6-Pad1)") (class "Default")
      (node (ref "EPD_C6") (pin "1") (pinfunction "1_1") (pintype "passive"))
      (node (ref "J1") (pin "18") (pinfunction "18_18") (pintype "bidirectional"))
    )
    (net (code "28") (name "Net-(EPD_C7-Pad1)") (class "Default")
      (node (ref "EPD_C7") (pin "1") (pinfunction "1_1") (pintype "passive"))
      (node (ref "J1") (pin "19") (pinfunction "19_19") (pintype "bidirectional"))
    )
    (net (code "29") (name "Net-(EPD_C8-Pad1)") (class "Default")
      (node (ref "EPD_C8") (pin "1") (pinfunction "1_1") (pintype "passive"))
      (node (ref "J1") (pin "20") (pinfunction "20_20") (pintype "bidirectional"))
    )
    (net (code "30") (name "Net-(EPD_C10-Pad1)") (class "Default")
      (node (ref "EPD_C10") (pin "1") (pinfunction "1_1") (pintype "passive"))
      (node (ref "J1") (pin "22") (pinfunction "22_22") (pintype "bidirectional"))
    )
    (net (code "31") (name "Net-(EPD_C12-Pad1)") (class "Default")
      (node (ref "EPD_C12") (pin "1") (pinfunction "1_1") (pintype "passive"))
      (node (ref "J1") (pin "24") (pinfunction "24_24") (pintype "bidirectional"))
    )
    (net (code "32") (name "Net-(IC1-CT)") (class "Default")
      (node (ref "C_DELAY") (pin "1") (pinfunction "1_1") (pintype "passive"))
      (node (ref "IC1") (pin "5") (pinfunction "CT_5") (pintype "bidirectional"))
    )
    (net (code "33") (name "Net-(J2-PadA5)") (class "Default")
      (node (ref "J2") (pin "A5") (pinfunction "A5_A5") (pintype "bidirectional"))
      (node (ref "R2-USB1") (pin "2") (pinfunction "2_2") (pintype "passive"))
    )
    (net (code "34") (name "Net-(J2-PadB5)") (class "Default")
      (node (ref "J2") (pin "B5") (pinfunction "B5_B5") (pintype "bidirectional"))
      (node (ref "R2-USB") (pin "1") (pinfunction "1_1") (pintype "passive"))
    )
    (net (code "35") (name "Net-(MCP73831-PROG)") (class "Default")
      (node (ref "MCP73831") (pin "5") (pinfunction "PROG_5") (pintype "input"))
      (node (ref "R2_BAT") (pin "2") (pinfunction "2_2") (pintype "passive"))
    )
    (net (code "36") (name "Net-(MCP73831-STAT)") (class "Default")
      (node (ref "MCP73831") (pin "1") (pinfunction "STAT_1") (pintype "output"))
      (node (ref "R1_BAT") (pin "1") (pinfunction "1_1") (pintype "passive"))
    )
    (net (code "37") (name "PREVGH") (class "Default")
      (node (ref "D5") (pin "1") (pinfunction "K_1") (pintype "bidirectional"))
      (node (ref "EPD_C9") (pin "1") (pinfunction "1_1") (pintype "passive"))
      (node (ref "J1") (pin "21") (pinfunction "21_21") (pintype "bidirectional"))
    )
    (net (code "38") (name "PREVGL") (class "Default")
      (node (ref "D4") (pin "2") (pinfunction "A_2") (pintype "bidirectional"))
      (node (ref "EPD_C11") (pin "1") (pinfunction "1_1") (pintype "passive"))
      (node (ref "J1") (pin "23") (pinfunction "23_23") (pintype "bidirectional"))
    )
    (net (code "39") (name "RESE") (class "Default")
      (node (ref "J1") (pin "3") (pinfunction "3_3") (pintype "bidirectional"))
      (node (ref "Q3") (pin "2") (pinfunction "S_2") (pintype "bidirectional"))
      (node (ref "R3") (pin "1") (pinfunction "1_1") (pintype "passive"))
    )
    (net (code "40") (name "RESE'") (class "Default")
      (node (ref "R2") (pin "2") (pinfunction "2_2") (pintype "passive"))
      (node (ref "R3") (pin "2") (pinfunction "2_2") (pintype "passive"))
      (node (ref "SJ1") (pin "2") (pinfunction "2_2") (pintype "passive"))
    )
    (net (code "41") (name "RESET") (class "Default")
      (node (ref "C5") (pin "1") (pinfunction "1_1") (pintype "passive"))
      (node (ref "IC1") (pin "1") (pinfunction "VOUT_1") (pintype "bidirectional"))
      (node (ref "RESET_BUTTON") (pin "3") (pinfunction "3_3") (pintype "passive"))
      (node (ref "RESET_BUTTON") (pin "4") (pinfunction "4_4") (pintype "passive"))
      (node (ref "R_RESET") (pin "2") (pinfunction "2_2") (pintype "passive"))
      (node (ref "U2") (pin "3") (pinfunction "EN_3") (pintype "input"))
    )
    (net (code "42") (name "RTC_RST") (class "Default")
      (node (ref "U2") (pin "16") (pinfunction "IO18_16") (pintype "bidirectional"))
      (node (ref "U3") (pin "4") (pinfunction "~{RST}_4") (pintype "input"))
    )
    (net (code "43") (name "RX") (class "Default")
      (node (ref "TP2") (pin "TP") (pinfunction "TP_TP") (pintype "input"))
      (node (ref "U2") (pin "24") (pinfunction "RXD0/GPIO17_24") (pintype "bidirectional"))
    )
    (net (code "44") (name "SCK") (class "Default")
      (node (ref "D10") (pin "1") (pinfunction "1_1") (pintype "passive"))
      (node (ref "J1") (pin "13") (pinfunction "13_13") (pintype "bidirectional"))
      (node (ref "J4") (pin "P5") (pinfunction "CLK_P5") (pintype "bidirectional"))
      (node (ref "R6") (pin "1") (pinfunction "1_1") (pintype "passive"))
      (node (ref "TP8") (pin "TP") (pinfunction "TP_TP") (pintype "input"))
      (node (ref "U1") (pin "6") (pinfunction "CLK_6") (pintype "input"))
      (node (ref "U2") (pin "6") (pinfunction "IO6_6") (pintype "bidirectional"))
    )
    (net (code "45") (name "SCL") (class "Default")
      (node (ref "J3") (pin "4") (pinfunction "4_4") (pintype "passive"))
      (node (ref "R2_PINH") (pin "1") (pinfunction "1_1") (pintype "passive"))
      (node (ref "SENSOR2") (pin "4") (pinfunction "SCK_4") (pintype "input"))
      (node (ref "U2") (pin "20") (pinfunction "IO22_20") (pintype "bidirectional"))
      (node (ref "U3") (pin "16") (pinfunction "SCL_16") (pintype "input"))
      (node (ref "U4") (pin "7") (pinfunction "SCL_7") (pintype "input"))
    )
    (net (code "46") (name "SDA") (class "Default")
      (node (ref "J3") (pin "3") (pinfunction "3_3") (pintype "passive"))
      (node (ref "R1_PINH") (pin "1") (pinfunction "1_1") (pintype "passive"))
      (node (ref "SENSOR2") (pin "3") (pinfunction "SDI_3") (pintype "bidirectional"))
      (node (ref "U2") (pin "19") (pinfunction "IO21_19") (pintype "bidirectional"))
      (node (ref "U3") (pin "15") (pinfunction "SDA_15") (pintype "bidirectional"))
      (node (ref "U4") (pin "8") (pinfunction "SDA_8") (pintype "bidirectional"))
    )
    (net (code "47") (name "SRC") (class "Default")
      (node (ref "C4") (pin "2") (pinfunction "2_2") (pintype "passive"))
      (node (ref "D5") (pin "2") (pinfunction "A_2") (pintype "bidirectional"))
      (node (ref "L1") (pin "1") (pinfunction "1_1") (pintype "passive"))
      (node (ref "Q3") (pin "3") (pinfunction "D_3") (pintype "bidirectional"))
    )
    (net (code "48") (name "SS_SD") (class "Default")
      (node (ref "D8") (pin "1") (pinfunction "1_1") (pintype "passive"))
      (node (ref "J4") (pin "P2") (pinfunction "CD/DAT3_P2") (pintype "bidirectional"))
      (node (ref "R10") (pin "1") (pinfunction "1_1") (pintype "passive"))
      (node (ref "U2") (pin "4") (pinfunction "IO4_4") (pintype "bidirectional"))
    )
    (net (code "49") (name "TX") (class "Default")
      (node (ref "TP1") (pin "TP") (pinfunction "TP_TP") (pintype "input"))
      (node (ref "U2") (pin "25") (pinfunction "TXD0/GPIO16_25") (pintype "bidirectional"))
    )
    (net (code "50") (name "USB_D+") (class "Default")
      (node (ref "D1") (pin "1") (pinfunction "I/O1_1_1") (pintype "bidirectional"))
      (node (ref "U2") (pin "14") (pinfunction "IO13_14") (pintype "bidirectional"))
    )
    (net (code "51") (name "USB_D-") (class "Default")
      (node (ref "D1") (pin "3") (pinfunction "I/O2_1_3") (pintype "bidirectional"))
      (node (ref "U2") (pin "13") (pinfunction "IO12_13") (pintype "bidirectional"))
    )
    (net (code "52") (name "VBAT") (class "Default")
      (node (ref "C2_BAT") (pin "1") (pinfunction "1_1") (pintype "passive"))
      (node (ref "MCP73831") (pin "3") (pinfunction "VBAT_3") (pintype "power_in"))
      (node (ref "Q1") (pin "3") (pinfunction "D_3") (pintype "bidirectional"))
      (node (ref "TP3") (pin "TP") (pinfunction "TP_TP") (pintype "input"))
      (node (ref "U4") (pin "2") (pinfunction "CELL_2") (pintype "power_in"))
      (node (ref "U4") (pin "3") (pinfunction "VDD_3") (pintype "power_in"))
    )
    (net (code "53") (name "VBUS") (class "Default")
      (node (ref "C1_BAT") (pin "1") (pinfunction "1_1") (pintype "passive"))
      (node (ref "C4_USB") (pin "1") (pinfunction "1_1") (pintype "passive"))
      (node (ref "C5_USB") (pin "1") (pinfunction "1_1") (pintype "passive"))
      (node (ref "CHG_LED") (pin "A") (pinfunction "A_A") (pintype "passive"))
      (node (ref "D1") (pin "5") (pinfunction "VBUS_5") (pintype "bidirectional"))
      (node (ref "D2") (pin "2") (pinfunction "ANODE_2") (pintype "bidirectional"))
      (node (ref "MCP73831") (pin "4") (pinfunction "VIN_4") (pintype "power_in"))
      (node (ref "PFMF.050.1") (pin "2") (pinfunction "2_2") (pintype "passive"))
      (node (ref "Q1") (pin "1") (pinfunction "G_1") (pintype "bidirectional"))
      (node (ref "R1_PWRUSB") (pin "2") (pinfunction "2_2") (pintype "passive"))
      (node (ref "TP14") (pin "TP") (pinfunction "TP_TP") (pintype "input"))
    )
    (net (code "54") (name "VRTC") (class "Default")
      (node (ref "C10_SUPERCAP") (pin "2") (pinfunction "2_2") (pintype "passive"))
      (node (ref "C8") (pin "1") (pinfunction "1_1") (pintype "passive"))
      (node (ref "R_CAPACITOR") (pin "2") (pinfunction "2_2") (pintype "passive"))
      (node (ref "U3") (pin "14") (pinfunction "VBAT_14") (pintype "power_in"))
    )
    (net (code "55") (name "VUSB") (class "Default")
      (node (ref "J2") (pin "A4") (pinfunction "A4_A4") (pintype "bidirectional"))
      (node (ref "J2") (pin "A9") (pinfunction "A9_A9") (pintype "bidirectional"))
      (node (ref "J2") (pin "B4") (pinfunction "B4_B4") (pintype "bidirectional"))
      (node (ref "J2") (pin "B9") (pinfunction "B9_B9") (pintype "bidirectional"))
      (node (ref "PFMF.050.1") (pin "1") (pinfunction "1_1") (pintype "passive"))
    )
    (net (code "56") (name "unconnected-(IC1-NC-Pad4)") (class "Default")
      (node (ref "IC1") (pin "4") (pinfunction "NC_4") (pintype "no_connect"))
    )
    (net (code "57") (name "unconnected-(IC4-NC-Pad4)") (class "Default")
      (node (ref "IC4") (pin "4") (pinfunction "NC_4") (pintype "no_connect"))
    )
    (net (code "58") (name "unconnected-(J1-Pad1)") (class "Default")
      (node (ref "J1") (pin "1") (pinfunction "1_1") (pintype "bidirectional"))
    )
    (net (code "59") (name "unconnected-(J1-Pad6)") (class "Default")
      (node (ref "J1") (pin "6") (pinfunction "6_6") (pintype "bidirectional"))
    )
    (net (code "60") (name "unconnected-(J1-Pad7)") (class "Default")
      (node (ref "J1") (pin "7") (pinfunction "7_7") (pintype "bidirectional"))
    )
    (net (code "61") (name "unconnected-(J2-PadA8)") (class "Default")
      (node (ref "J2") (pin "A8") (pinfunction "A8_A8") (pintype "bidirectional"))
    )
    (net (code "62") (name "unconnected-(J2-PadB8)") (class "Default")
      (node (ref "J2") (pin "B8") (pinfunction "B8_B8") (pintype "bidirectional"))
    )
    (net (code "63") (name "unconnected-(J4-DAT1-PadP8)") (class "Default")
      (node (ref "J4") (pin "P8") (pinfunction "DAT1_P8") (pintype "bidirectional"))
    )
    (net (code "64") (name "unconnected-(J4-DAT2-PadP1)") (class "Default")
      (node (ref "J4") (pin "P1") (pinfunction "DAT2_P1") (pintype "bidirectional"))
    )
    (net (code "65") (name "unconnected-(J4-DETECTION_1-PadS1)") (class "Default")
      (node (ref "J4") (pin "S1") (pinfunction "DETECTION_1_S1") (pintype "bidirectional"))
    )
    (net (code "66") (name "unconnected-(J4-DETECTION_2-PadS2)") (class "Default")
      (node (ref "J4") (pin "S2") (pinfunction "DETECTION_2_S2") (pintype "bidirectional"))
    )
    (net (code "67") (name "unconnected-(U2-NC-Pad22)") (class "Default")
      (node (ref "U2") (pin "22") (pinfunction "NC_22") (pintype "no_connect"))
    )
    (net (code "68") (name "unconnected-(U4-~{ALERT}-Pad5)") (class "Default")
      (node (ref "U4") (pin "5") (pinfunction "~{ALERT}_5") (pintype "output"))
    )
  )
)
